# mega_shield2.net
KiCad netlist of a schematic drawn in EAGLE
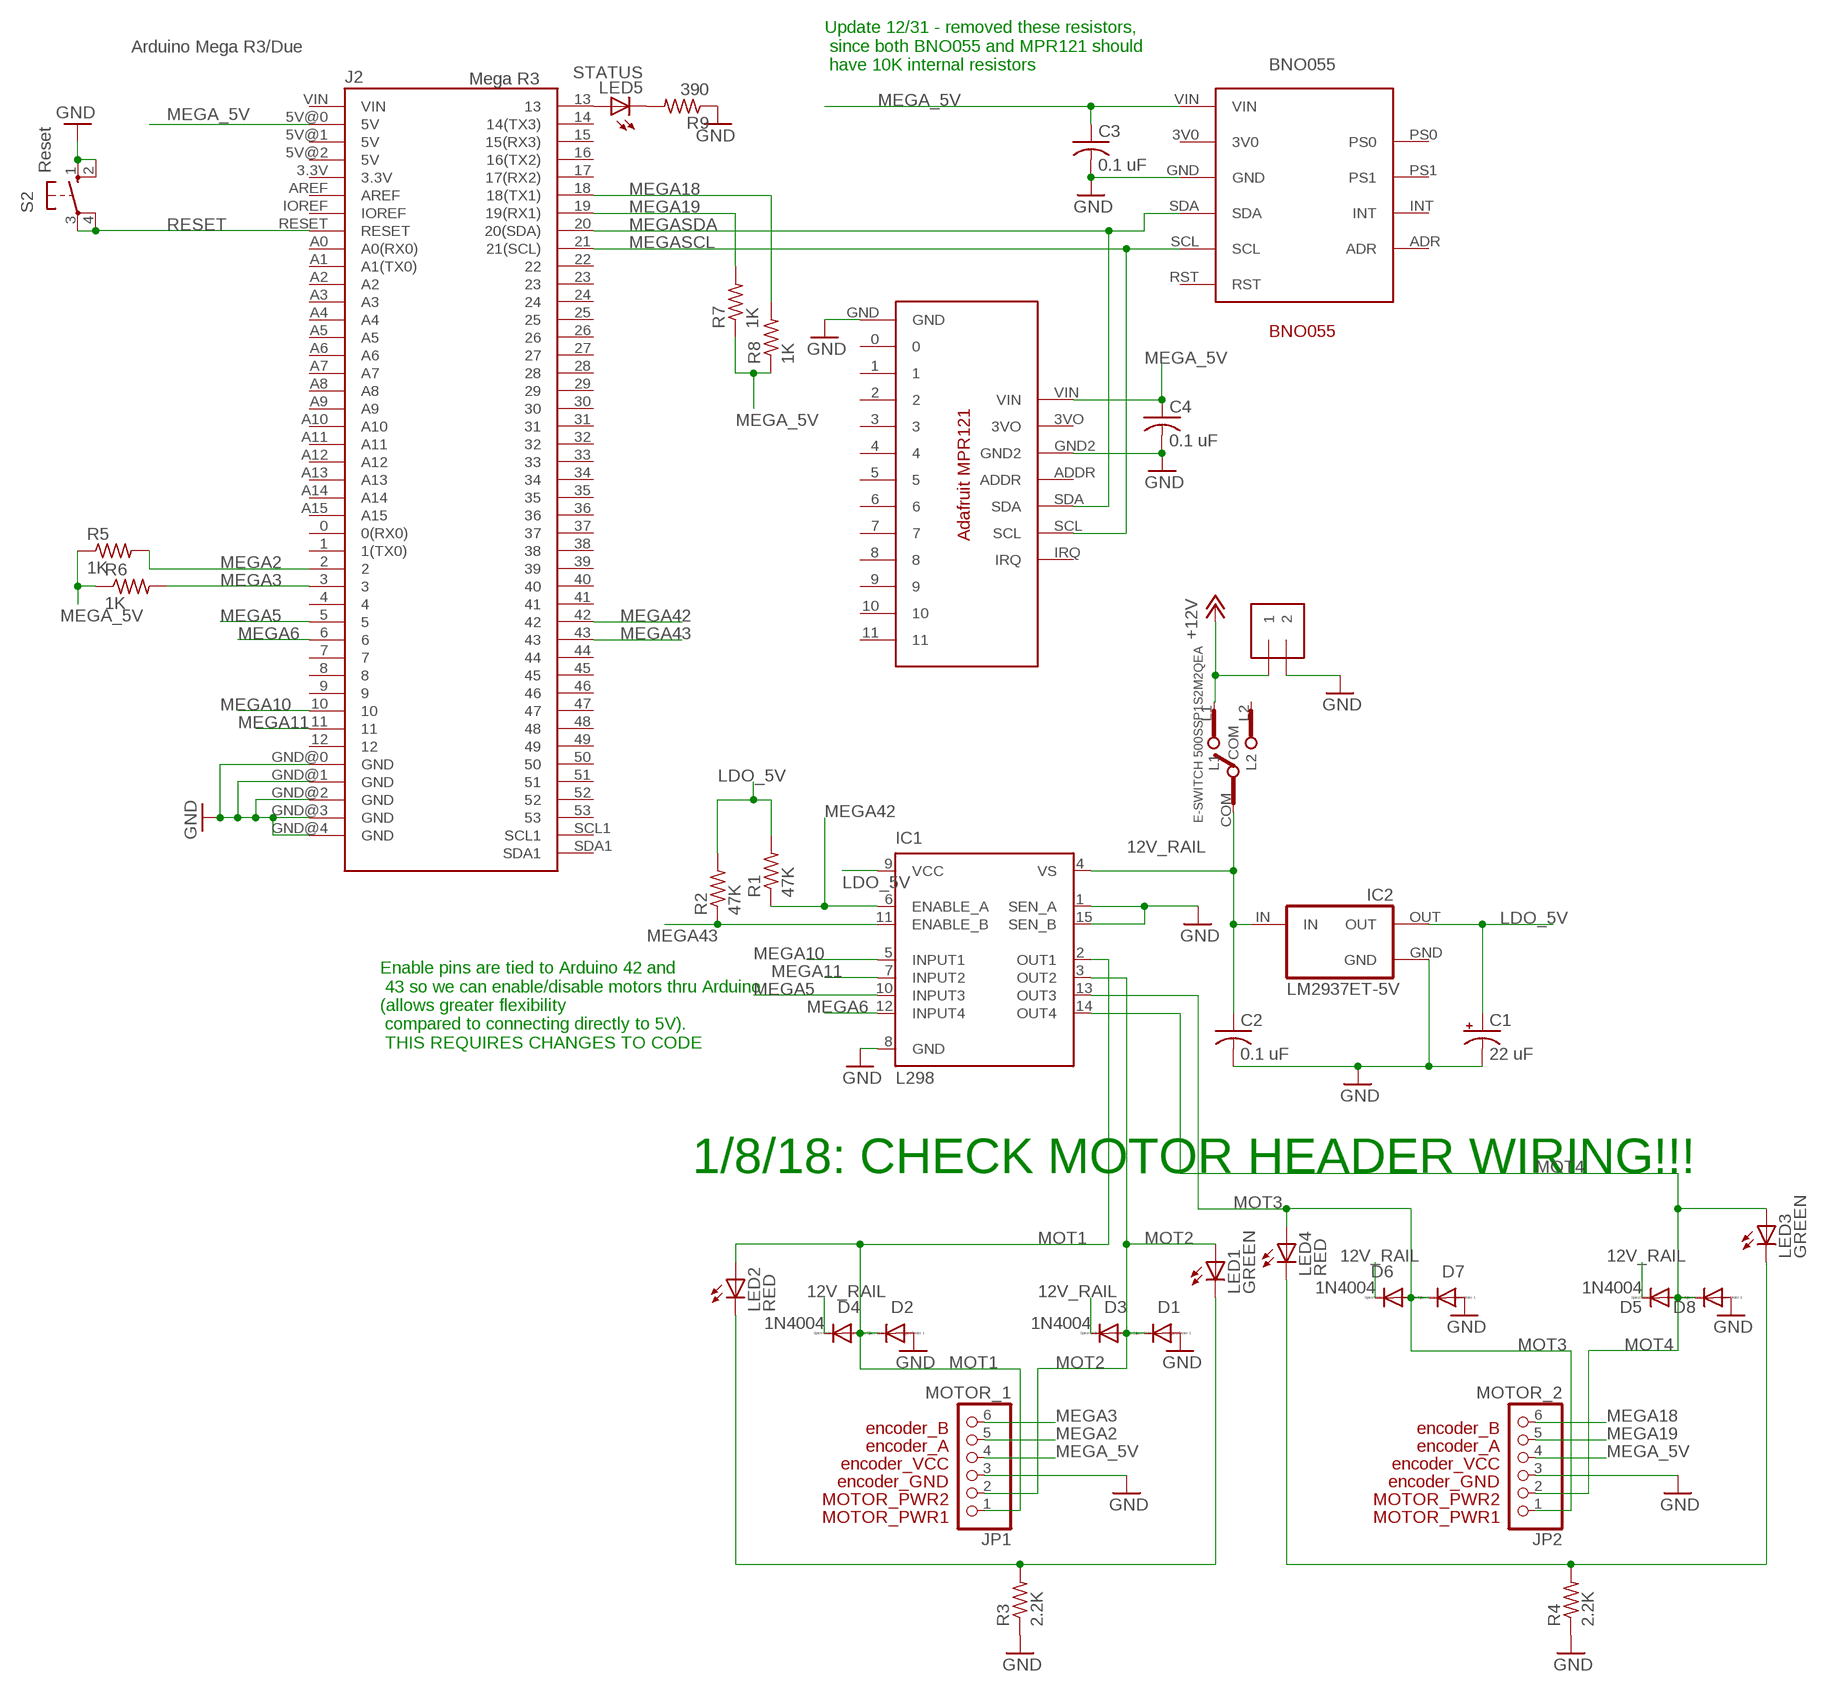
[diagram p0: schematic, sheet 1]

(export (version "E")
  (design (tool "Eeschema 10.0.6"))
  (components
    (comp (ref "12V_IN")
      (value "1X2-3.5MM")
      (footprint "eagle-import:1X2-3.5MM")
      (libsource (lib "eagle-import") (part "1X2-3.5MM"))
    )
    (comp (ref "BNO055")
      (value "BNO055")
      (footprint "eagle-import:BNO055")
      (libsource (lib "eagle-import") (part "BNO055"))
    )
    (comp (ref "C1")
      (value "22 uF")
      (footprint "eagle-import:B45181A")
      (libsource (lib "eagle-import") (part "CPOL-USB45181A"))
    )
    (comp (ref "C2")
      (value "0.1 uF")
      (footprint "eagle-import:C025-050X050")
      (libsource (lib "eagle-import") (part "C-US025-050X050"))
    )
    (comp (ref "C3")
      (value "0.1 uF")
      (footprint "eagle-import:C025-050X050")
      (libsource (lib "eagle-import") (part "C-US025-050X050"))
    )
    (comp (ref "C4")
      (value "0.1 uF")
      (footprint "eagle-import:C025-050X050")
      (libsource (lib "eagle-import") (part "C-US025-050X050"))
    )
    (comp (ref "D1")
      (value "1N4004")
      (footprint "eagle-import:DO41-10")
      (libsource (lib "eagle-import") (part "1N4004"))
    )
    (comp (ref "D2")
      (value "1N4004")
      (footprint "eagle-import:DO41-10")
      (libsource (lib "eagle-import") (part "1N4004"))
    )
    (comp (ref "D3")
      (value "1N4004")
      (footprint "eagle-import:DO41-10")
      (libsource (lib "eagle-import") (part "1N4004"))
    )
    (comp (ref "D4")
      (value "1N4004")
      (footprint "eagle-import:DO41-10")
      (libsource (lib "eagle-import") (part "1N4004"))
    )
    (comp (ref "D5")
      (value "1N4004")
      (footprint "eagle-import:DO41-10")
      (libsource (lib "eagle-import") (part "1N4004"))
    )
    (comp (ref "D6")
      (value "1N4004")
      (footprint "eagle-import:DO41-10")
      (libsource (lib "eagle-import") (part "1N4004"))
    )
    (comp (ref "D7")
      (value "1N4004")
      (footprint "eagle-import:DO41-10")
      (libsource (lib "eagle-import") (part "1N4004"))
    )
    (comp (ref "D8")
      (value "1N4004")
      (footprint "eagle-import:DO41-10")
      (libsource (lib "eagle-import") (part "1N4004"))
    )
    (comp (ref "IC1")
      (value "L298")
      (footprint "eagle-import:MULTIWATT-15")
      (fields (field (name "MPN") "L298N"))
      (libsource (lib "eagle-import") (part "L298"))
    )
    (comp (ref "IC2")
      (value "LM2937ET-5V")
      (footprint "eagle-import:TO220(V)")
      (libsource (lib "eagle-import") (part "LM2937ET-5,0"))
    )
    (comp (ref "J2")
      (value "Mega R3")
      (footprint "eagle-import:ARDUINO_MEGA")
      (libsource (lib "eagle-import") (part "ARDUINO-MEGAFULL"))
    )
    (comp (ref "JP1")
      (value "MOTOR_1")
      (footprint "eagle-import:1X06")
      (libsource (lib "eagle-import") (part "PINHD-1X6"))
    )
    (comp (ref "JP2")
      (value "MOTOR_2")
      (footprint "eagle-import:1X06")
      (libsource (lib "eagle-import") (part "PINHD-1X6"))
    )
    (comp (ref "LED1")
      (value "GREEN")
      (footprint "eagle-import:LED3MM")
      (libsource (lib "eagle-import") (part "LED3MM"))
    )
    (comp (ref "LED2")
      (value "RED")
      (footprint "eagle-import:LED3MM")
      (libsource (lib "eagle-import") (part "LED3MM"))
    )
    (comp (ref "LED3")
      (value "GREEN")
      (footprint "eagle-import:LED3MM")
      (libsource (lib "eagle-import") (part "LED3MM"))
    )
    (comp (ref "LED4")
      (value "RED")
      (footprint "eagle-import:LED3MM")
      (libsource (lib "eagle-import") (part "LED3MM"))
    )
    (comp (ref "LED5")
      (value "STATUS")
      (footprint "eagle-import:LED3MM")
      (libsource (lib "eagle-import") (part "LED3MM"))
    )
    (comp (ref "MPR121")
      (value "ADA_MPR121")
      (footprint "eagle-import:ADA_MPR121")
      (libsource (lib "eagle-import") (part "ADA_MPR121"))
    )
    (comp (ref "R1")
      (value "47K")
      (footprint "eagle-import:0207_10")
      (libsource (lib "eagle-import") (part "R-US_0207/10"))
    )
    (comp (ref "R2")
      (value "47K")
      (footprint "eagle-import:0207_10")
      (libsource (lib "eagle-import") (part "R-US_0207/10"))
    )
    (comp (ref "R3")
      (value "2.2K")
      (footprint "eagle-import:0207_10")
      (libsource (lib "eagle-import") (part "R-US_0207/10"))
    )
    (comp (ref "R4")
      (value "2.2K")
      (footprint "eagle-import:0207_10")
      (libsource (lib "eagle-import") (part "R-US_0207/10"))
    )
    (comp (ref "R5")
      (value "1K")
      (footprint "eagle-import:0207_10")
      (libsource (lib "eagle-import") (part "R-US_0207/10"))
    )
    (comp (ref "R6")
      (value "1K")
      (footprint "eagle-import:0207_10")
      (libsource (lib "eagle-import") (part "R-US_0207/10"))
    )
    (comp (ref "R7")
      (value "1K")
      (footprint "eagle-import:0207_10")
      (libsource (lib "eagle-import") (part "R-US_0207/10"))
    )
    (comp (ref "R8")
      (value "1K")
      (footprint "eagle-import:0207_10")
      (libsource (lib "eagle-import") (part "R-US_0207/10"))
    )
    (comp (ref "R9")
      (value "390")
      (footprint "eagle-import:0207_10")
      (libsource (lib "eagle-import") (part "R-US_0207/10"))
    )
    (comp (ref "S2")
      (value "Reset")
      (footprint "eagle-import:B3F-10XX")
      (fields (field (name "MPN") "B3F-1000"))
      (libsource (lib "eagle-import") (part "10-XX"))
    )
    (comp (ref "SLIDE_SW")
      (value "E-SWITCH_500SSP1S2M2QEA")
      (footprint "eagle-import:E-SWITCH_500SSP1S2M2QEA")
      (libsource (lib "eagle-import") (part "E-SWITCH_500SSP1S2M2QEA"))
    )
  )
  (nets
    (net (code "1") (name "+12V") (class "Default")
      (node (ref "12V_IN") (pin "1") (pinfunction "1_1") (pintype "passive"))
      (node (ref "SLIDE_SW") (pin "L1") (pinfunction "L1_L1") (pintype "bidirectional"))
    )
    (net (code "2") (name "/12V_RAIL") (class "Default")
      (node (ref "C2") (pin "1") (pinfunction "1_1") (pintype "passive"))
      (node (ref "D3") (pin "C") (pinfunction "C_C") (pintype "passive"))
      (node (ref "D4") (pin "C") (pinfunction "C_C") (pintype "passive"))
      (node (ref "D5") (pin "C") (pinfunction "C_C") (pintype "passive"))
      (node (ref "D6") (pin "C") (pinfunction "C_C") (pintype "passive"))
      (node (ref "IC1") (pin "4") (pinfunction "VS_4") (pintype "power_in"))
      (node (ref "IC2") (pin "IN") (pinfunction "IN_IN") (pintype "input"))
      (node (ref "SLIDE_SW") (pin "COM") (pinfunction "COM_COM") (pintype "bidirectional"))
    )
    (net (code "3") (name "/LDO_5V") (class "Default")
      (node (ref "C1") (pin "+") (pinfunction "+_+") (pintype "passive"))
      (node (ref "IC1") (pin "9") (pinfunction "VCC_9") (pintype "power_in"))
      (node (ref "IC2") (pin "OUT") (pinfunction "OUT_OUT") (pintype "output"))
      (node (ref "R1") (pin "2") (pinfunction "2_2") (pintype "passive"))
      (node (ref "R2") (pin "2") (pinfunction "2_2") (pintype "passive"))
    )
    (net (code "4") (name "/MEGA2") (class "Default")
      (node (ref "J2") (pin "2") (pinfunction "2_2") (pintype "bidirectional"))
      (node (ref "JP1") (pin "5") (pinfunction "5_5") (pintype "passive"))
      (node (ref "R5") (pin "2") (pinfunction "2_2") (pintype "passive"))
    )
    (net (code "5") (name "/MEGA3") (class "Default")
      (node (ref "J2") (pin "3") (pinfunction "3_3") (pintype "bidirectional"))
      (node (ref "JP1") (pin "6") (pinfunction "6_6") (pintype "passive"))
      (node (ref "R6") (pin "2") (pinfunction "2_2") (pintype "passive"))
    )
    (net (code "6") (name "/MEGA5") (class "Default")
      (node (ref "IC1") (pin "10") (pinfunction "INPUT3_10") (pintype "input"))
      (node (ref "J2") (pin "5") (pinfunction "5_5") (pintype "bidirectional"))
    )
    (net (code "7") (name "/MEGA6") (class "Default")
      (node (ref "IC1") (pin "12") (pinfunction "INPUT4_12") (pintype "input"))
      (node (ref "J2") (pin "6") (pinfunction "6_6") (pintype "bidirectional"))
    )
    (net (code "8") (name "/MEGA10") (class "Default")
      (node (ref "IC1") (pin "5") (pinfunction "INPUT1_5") (pintype "input"))
      (node (ref "J2") (pin "10") (pinfunction "10_10") (pintype "bidirectional"))
    )
    (net (code "9") (name "/MEGA11") (class "Default")
      (node (ref "IC1") (pin "7") (pinfunction "INPUT2_7") (pintype "input"))
      (node (ref "J2") (pin "11") (pinfunction "11_11") (pintype "bidirectional"))
    )
    (net (code "10") (name "/MEGA18") (class "Default")
      (node (ref "J2") (pin "18") (pinfunction "18(TX1)_18") (pintype "bidirectional"))
      (node (ref "JP2") (pin "6") (pinfunction "6_6") (pintype "passive"))
      (node (ref "R8") (pin "2") (pinfunction "2_2") (pintype "passive"))
    )
    (net (code "11") (name "/MEGA19") (class "Default")
      (node (ref "J2") (pin "19") (pinfunction "19(RX1)_19") (pintype "bidirectional"))
      (node (ref "JP2") (pin "5") (pinfunction "5_5") (pintype "passive"))
      (node (ref "R7") (pin "2") (pinfunction "2_2") (pintype "passive"))
    )
    (net (code "12") (name "/MEGA42") (class "Default")
      (node (ref "IC1") (pin "6") (pinfunction "ENABLE_A_6") (pintype "input"))
      (node (ref "J2") (pin "42") (pinfunction "42_42") (pintype "bidirectional"))
      (node (ref "R1") (pin "1") (pinfunction "1_1") (pintype "passive"))
    )
    (net (code "13") (name "/MEGA43") (class "Default")
      (node (ref "IC1") (pin "11") (pinfunction "ENABLE_B_11") (pintype "input"))
      (node (ref "J2") (pin "43") (pinfunction "43_43") (pintype "bidirectional"))
      (node (ref "R2") (pin "1") (pinfunction "1_1") (pintype "passive"))
    )
    (net (code "14") (name "/MEGASCL") (class "Default")
      (node (ref "BNO055") (pin "SCL") (pinfunction "SCL_SCL") (pintype "bidirectional"))
      (node (ref "J2") (pin "21") (pinfunction "21(SCL)_21") (pintype "bidirectional"))
      (node (ref "MPR121") (pin "SCL") (pinfunction "SCL_SCL") (pintype "bidirectional"))
    )
    (net (code "15") (name "/MEGASDA") (class "Default")
      (node (ref "BNO055") (pin "SDA") (pinfunction "SDA_SDA") (pintype "bidirectional"))
      (node (ref "J2") (pin "20") (pinfunction "20(SDA)_20") (pintype "bidirectional"))
      (node (ref "MPR121") (pin "SDA") (pinfunction "SDA_SDA") (pintype "bidirectional"))
    )
    (net (code "16") (name "/MEGA_5V") (class "Default")
      (node (ref "BNO055") (pin "VIN") (pinfunction "VIN_VIN") (pintype "bidirectional"))
      (node (ref "C3") (pin "1") (pinfunction "1_1") (pintype "passive"))
      (node (ref "C4") (pin "1") (pinfunction "1_1") (pintype "passive"))
      (node (ref "J2") (pin "5V@0") (pinfunction "5V_5V@0") (pintype "bidirectional"))
      (node (ref "JP1") (pin "4") (pinfunction "4_4") (pintype "passive"))
      (node (ref "JP2") (pin "4") (pinfunction "4_4") (pintype "passive"))
      (node (ref "MPR121") (pin "VIN") (pinfunction "VIN_VIN") (pintype "bidirectional"))
      (node (ref "R5") (pin "1") (pinfunction "1_1") (pintype "passive"))
      (node (ref "R6") (pin "1") (pinfunction "1_1") (pintype "passive"))
      (node (ref "R7") (pin "1") (pinfunction "1_1") (pintype "passive"))
      (node (ref "R8") (pin "1") (pinfunction "1_1") (pintype "passive"))
    )
    (net (code "17") (name "/MOT1") (class "Default")
      (node (ref "D2") (pin "C") (pinfunction "C_C") (pintype "passive"))
      (node (ref "D4") (pin "A") (pinfunction "A_A") (pintype "passive"))
      (node (ref "IC1") (pin "2") (pinfunction "OUT1_2") (pintype "output"))
      (node (ref "JP1") (pin "1") (pinfunction "1_1") (pintype "passive"))
      (node (ref "LED2") (pin "A") (pinfunction "A_A") (pintype "passive"))
    )
    (net (code "18") (name "/MOT2") (class "Default")
      (node (ref "D1") (pin "C") (pinfunction "C_C") (pintype "passive"))
      (node (ref "D3") (pin "A") (pinfunction "A_A") (pintype "passive"))
      (node (ref "IC1") (pin "3") (pinfunction "OUT2_3") (pintype "output"))
      (node (ref "JP1") (pin "2") (pinfunction "2_2") (pintype "passive"))
      (node (ref "LED1") (pin "A") (pinfunction "A_A") (pintype "passive"))
    )
    (net (code "19") (name "/MOT3") (class "Default")
      (node (ref "D6") (pin "A") (pinfunction "A_A") (pintype "passive"))
      (node (ref "D7") (pin "C") (pinfunction "C_C") (pintype "passive"))
      (node (ref "IC1") (pin "13") (pinfunction "OUT3_13") (pintype "output"))
      (node (ref "JP2") (pin "1") (pinfunction "1_1") (pintype "passive"))
      (node (ref "LED4") (pin "A") (pinfunction "A_A") (pintype "passive"))
    )
    (net (code "20") (name "/MOT4") (class "Default")
      (node (ref "D5") (pin "A") (pinfunction "A_A") (pintype "passive"))
      (node (ref "D8") (pin "C") (pinfunction "C_C") (pintype "passive"))
      (node (ref "IC1") (pin "14") (pinfunction "OUT4_14") (pintype "output"))
      (node (ref "JP2") (pin "2") (pinfunction "2_2") (pintype "passive"))
      (node (ref "LED3") (pin "A") (pinfunction "A_A") (pintype "passive"))
    )
    (net (code "21") (name "/RESET") (class "Default")
      (node (ref "J2") (pin "RESET") (pinfunction "RESET_RESET") (pintype "bidirectional"))
      (node (ref "S2") (pin "3") (pinfunction "P_3") (pintype "passive"))
      (node (ref "S2") (pin "4") (pinfunction "P1_4") (pintype "passive"))
    )
    (net (code "22") (name "GND") (class "Default")
      (node (ref "12V_IN") (pin "2") (pinfunction "2_2") (pintype "passive"))
      (node (ref "BNO055") (pin "GND") (pinfunction "GND_GND") (pintype "bidirectional"))
      (node (ref "C1") (pin "-") (pinfunction "-_-") (pintype "passive"))
      (node (ref "C2") (pin "2") (pinfunction "2_2") (pintype "passive"))
      (node (ref "C3") (pin "2") (pinfunction "2_2") (pintype "passive"))
      (node (ref "C4") (pin "2") (pinfunction "2_2") (pintype "passive"))
      (node (ref "D1") (pin "A") (pinfunction "A_A") (pintype "passive"))
      (node (ref "D2") (pin "A") (pinfunction "A_A") (pintype "passive"))
      (node (ref "D7") (pin "A") (pinfunction "A_A") (pintype "passive"))
      (node (ref "D8") (pin "A") (pinfunction "A_A") (pintype "passive"))
      (node (ref "IC1") (pin "1") (pinfunction "SEN_A_1") (pintype "input"))
      (node (ref "IC1") (pin "15") (pinfunction "SEN_B_15") (pintype "input"))
      (node (ref "IC1") (pin "8") (pinfunction "GND_8") (pintype "power_in"))
      (node (ref "IC2") (pin "GND") (pinfunction "GND_GND") (pintype "power_in"))
      (node (ref "J2") (pin "GND@0") (pinfunction "GND_GND@0") (pintype "bidirectional"))
      (node (ref "J2") (pin "GND@1") (pinfunction "GND_GND@1") (pintype "bidirectional"))
      (node (ref "J2") (pin "GND@2") (pinfunction "GND_GND@2") (pintype "bidirectional"))
      (node (ref "J2") (pin "GND@3") (pinfunction "GND_GND@3") (pintype "bidirectional"))
      (node (ref "J2") (pin "GND@4") (pinfunction "GND_GND@4") (pintype "bidirectional"))
      (node (ref "JP1") (pin "3") (pinfunction "3_3") (pintype "passive"))
      (node (ref "JP2") (pin "3") (pinfunction "3_3") (pintype "passive"))
      (node (ref "MPR121") (pin "GND") (pinfunction "GND_GND") (pintype "bidirectional"))
      (node (ref "MPR121") (pin "GND2") (pinfunction "GND2_GND2") (pintype "bidirectional"))
      (node (ref "R3") (pin "1") (pinfunction "1_1") (pintype "passive"))
      (node (ref "R4") (pin "1") (pinfunction "1_1") (pintype "passive"))
      (node (ref "R9") (pin "1") (pinfunction "1_1") (pintype "passive"))
      (node (ref "S2") (pin "1") (pinfunction "S_1") (pintype "passive"))
      (node (ref "S2") (pin "2") (pinfunction "S1_2") (pintype "passive"))
    )
    (net (code "23") (name "Net-(J2-Pad13)") (class "Default")
      (node (ref "J2") (pin "13") (pinfunction "13_13") (pintype "bidirectional"))
      (node (ref "LED5") (pin "A") (pinfunction "A_A") (pintype "passive"))
    )
    (net (code "24") (name "Net-(LED1-C)") (class "Default")
      (node (ref "LED1") (pin "K") (pinfunction "C_K") (pintype "passive"))
      (node (ref "LED2") (pin "K") (pinfunction "C_K") (pintype "passive"))
      (node (ref "R3") (pin "2") (pinfunction "2_2") (pintype "passive"))
    )
    (net (code "25") (name "Net-(LED3-C)") (class "Default")
      (node (ref "LED3") (pin "K") (pinfunction "C_K") (pintype "passive"))
      (node (ref "LED4") (pin "K") (pinfunction "C_K") (pintype "passive"))
      (node (ref "R4") (pin "2") (pinfunction "2_2") (pintype "passive"))
    )
    (net (code "26") (name "Net-(LED5-C)") (class "Default")
      (node (ref "LED5") (pin "K") (pinfunction "C_K") (pintype "passive"))
      (node (ref "R9") (pin "2") (pinfunction "2_2") (pintype "passive"))
    )
    (net (code "27") (name "unconnected-(BNO055-Pad3V0)") (class "Default")
      (node (ref "BNO055") (pin "3V0") (pinfunction "3V0_3V0") (pintype "bidirectional"))
    )
    (net (code "28") (name "unconnected-(BNO055-PadADR)") (class "Default")
      (node (ref "BNO055") (pin "ADR") (pinfunction "ADR_ADR") (pintype "bidirectional"))
    )
    (net (code "29") (name "unconnected-(BNO055-PadINT)") (class "Default")
      (node (ref "BNO055") (pin "INT") (pinfunction "INT_INT") (pintype "bidirectional"))
    )
    (net (code "30") (name "unconnected-(BNO055-PadPS0)") (class "Default")
      (node (ref "BNO055") (pin "PS0") (pinfunction "PS0_PS0") (pintype "bidirectional"))
    )
    (net (code "31") (name "unconnected-(BNO055-PadPS1)") (class "Default")
      (node (ref "BNO055") (pin "PS1") (pinfunction "PS1_PS1") (pintype "bidirectional"))
    )
    (net (code "32") (name "unconnected-(BNO055-PadRST)") (class "Default")
      (node (ref "BNO055") (pin "RST") (pinfunction "RST_RST") (pintype "bidirectional"))
    )
    (net (code "33") (name "unconnected-(J2-0(RX0)-Pad0)") (class "Default")
      (node (ref "J2") (pin "0") (pinfunction "0(RX0)_0") (pintype "bidirectional"))
    )
    (net (code "34") (name "unconnected-(J2-1(TX0)-Pad1)") (class "Default")
      (node (ref "J2") (pin "1") (pinfunction "1(TX0)_1") (pintype "bidirectional"))
    )
    (net (code "35") (name "unconnected-(J2-5V-Pad5V@1)") (class "Default")
      (node (ref "J2") (pin "5V@1") (pinfunction "5V_5V@1") (pintype "bidirectional"))
    )
    (net (code "36") (name "unconnected-(J2-5V-Pad5V@2)") (class "Default")
      (node (ref "J2") (pin "5V@2") (pinfunction "5V_5V@2") (pintype "bidirectional"))
    )
    (net (code "37") (name "unconnected-(J2-14(TX3)-Pad14)") (class "Default")
      (node (ref "J2") (pin "14") (pinfunction "14(TX3)_14") (pintype "bidirectional"))
    )
    (net (code "38") (name "unconnected-(J2-15(RX3)-Pad15)") (class "Default")
      (node (ref "J2") (pin "15") (pinfunction "15(RX3)_15") (pintype "bidirectional"))
    )
    (net (code "39") (name "unconnected-(J2-16(TX2)-Pad16)") (class "Default")
      (node (ref "J2") (pin "16") (pinfunction "16(TX2)_16") (pintype "bidirectional"))
    )
    (net (code "40") (name "unconnected-(J2-17(RX2)-Pad17)") (class "Default")
      (node (ref "J2") (pin "17") (pinfunction "17(RX2)_17") (pintype "bidirectional"))
    )
    (net (code "41") (name "unconnected-(J2-A0(RX0)-PadA0)") (class "Default")
      (node (ref "J2") (pin "A0") (pinfunction "A0(RX0)_A0") (pintype "bidirectional"))
    )
    (net (code "42") (name "unconnected-(J2-A1(TX0)-PadA1)") (class "Default")
      (node (ref "J2") (pin "A1") (pinfunction "A1(TX0)_A1") (pintype "bidirectional"))
    )
    (net (code "43") (name "unconnected-(J2-Pad3.3V)") (class "Default")
      (node (ref "J2") (pin "3.3V") (pinfunction "3.3V_3.3V") (pintype "bidirectional"))
    )
    (net (code "44") (name "unconnected-(J2-Pad4)") (class "Default")
      (node (ref "J2") (pin "4") (pinfunction "4_4") (pintype "bidirectional"))
    )
    (net (code "45") (name "unconnected-(J2-Pad7)") (class "Default")
      (node (ref "J2") (pin "7") (pinfunction "7_7") (pintype "bidirectional"))
    )
    (net (code "46") (name "unconnected-(J2-Pad8)") (class "Default")
      (node (ref "J2") (pin "8") (pinfunction "8_8") (pintype "bidirectional"))
    )
    (net (code "47") (name "unconnected-(J2-Pad9)") (class "Default")
      (node (ref "J2") (pin "9") (pinfunction "9_9") (pintype "bidirectional"))
    )
    (net (code "48") (name "unconnected-(J2-Pad12)") (class "Default")
      (node (ref "J2") (pin "12") (pinfunction "12_12") (pintype "bidirectional"))
    )
    (net (code "49") (name "unconnected-(J2-Pad22)") (class "Default")
      (node (ref "J2") (pin "22") (pinfunction "22_22") (pintype "bidirectional"))
    )
    (net (code "50") (name "unconnected-(J2-Pad23)") (class "Default")
      (node (ref "J2") (pin "23") (pinfunction "23_23") (pintype "bidirectional"))
    )
    (net (code "51") (name "unconnected-(J2-Pad24)") (class "Default")
      (node (ref "J2") (pin "24") (pinfunction "24_24") (pintype "bidirectional"))
    )
    (net (code "52") (name "unconnected-(J2-Pad25)") (class "Default")
      (node (ref "J2") (pin "25") (pinfunction "25_25") (pintype "bidirectional"))
    )
    (net (code "53") (name "unconnected-(J2-Pad26)") (class "Default")
      (node (ref "J2") (pin "26") (pinfunction "26_26") (pintype "bidirectional"))
    )
    (net (code "54") (name "unconnected-(J2-Pad27)") (class "Default")
      (node (ref "J2") (pin "27") (pinfunction "27_27") (pintype "bidirectional"))
    )
    (net (code "55") (name "unconnected-(J2-Pad28)") (class "Default")
      (node (ref "J2") (pin "28") (pinfunction "28_28") (pintype "bidirectional"))
    )
    (net (code "56") (name "unconnected-(J2-Pad29)") (class "Default")
      (node (ref "J2") (pin "29") (pinfunction "29_29") (pintype "bidirectional"))
    )
    (net (code "57") (name "unconnected-(J2-Pad30)") (class "Default")
      (node (ref "J2") (pin "30") (pinfunction "30_30") (pintype "bidirectional"))
    )
    (net (code "58") (name "unconnected-(J2-Pad31)") (class "Default")
      (node (ref "J2") (pin "31") (pinfunction "31_31") (pintype "bidirectional"))
    )
    (net (code "59") (name "unconnected-(J2-Pad32)") (class "Default")
      (node (ref "J2") (pin "32") (pinfunction "32_32") (pintype "bidirectional"))
    )
    (net (code "60") (name "unconnected-(J2-Pad33)") (class "Default")
      (node (ref "J2") (pin "33") (pinfunction "33_33") (pintype "bidirectional"))
    )
    (net (code "61") (name "unconnected-(J2-Pad34)") (class "Default")
      (node (ref "J2") (pin "34") (pinfunction "34_34") (pintype "bidirectional"))
    )
    (net (code "62") (name "unconnected-(J2-Pad35)") (class "Default")
      (node (ref "J2") (pin "35") (pinfunction "35_35") (pintype "bidirectional"))
    )
    (net (code "63") (name "unconnected-(J2-Pad36)") (class "Default")
      (node (ref "J2") (pin "36") (pinfunction "36_36") (pintype "bidirectional"))
    )
    (net (code "64") (name "unconnected-(J2-Pad37)") (class "Default")
      (node (ref "J2") (pin "37") (pinfunction "37_37") (pintype "bidirectional"))
    )
    (net (code "65") (name "unconnected-(J2-Pad38)") (class "Default")
      (node (ref "J2") (pin "38") (pinfunction "38_38") (pintype "bidirectional"))
    )
    (net (code "66") (name "unconnected-(J2-Pad39)") (class "Default")
      (node (ref "J2") (pin "39") (pinfunction "39_39") (pintype "bidirectional"))
    )
    (net (code "67") (name "unconnected-(J2-Pad40)") (class "Default")
      (node (ref "J2") (pin "40") (pinfunction "40_40") (pintype "bidirectional"))
    )
    (net (code "68") (name "unconnected-(J2-Pad41)") (class "Default")
      (node (ref "J2") (pin "41") (pinfunction "41_41") (pintype "bidirectional"))
    )
    (net (code "69") (name "unconnected-(J2-Pad44)") (class "Default")
      (node (ref "J2") (pin "44") (pinfunction "44_44") (pintype "bidirectional"))
    )
    (net (code "70") (name "unconnected-(J2-Pad45)") (class "Default")
      (node (ref "J2") (pin "45") (pinfunction "45_45") (pintype "bidirectional"))
    )
    (net (code "71") (name "unconnected-(J2-Pad46)") (class "Default")
      (node (ref "J2") (pin "46") (pinfunction "46_46") (pintype "bidirectional"))
    )
    (net (code "72") (name "unconnected-(J2-Pad47)") (class "Default")
      (node (ref "J2") (pin "47") (pinfunction "47_47") (pintype "bidirectional"))
    )
    (net (code "73") (name "unconnected-(J2-Pad48)") (class "Default")
      (node (ref "J2") (pin "48") (pinfunction "48_48") (pintype "bidirectional"))
    )
    (net (code "74") (name "unconnected-(J2-Pad49)") (class "Default")
      (node (ref "J2") (pin "49") (pinfunction "49_49") (pintype "bidirectional"))
    )
    (net (code "75") (name "unconnected-(J2-Pad50)") (class "Default")
      (node (ref "J2") (pin "50") (pinfunction "50_50") (pintype "bidirectional"))
    )
    (net (code "76") (name "unconnected-(J2-Pad51)") (class "Default")
      (node (ref "J2") (pin "51") (pinfunction "51_51") (pintype "bidirectional"))
    )
    (net (code "77") (name "unconnected-(J2-Pad52)") (class "Default")
      (node (ref "J2") (pin "52") (pinfunction "52_52") (pintype "bidirectional"))
    )
    (net (code "78") (name "unconnected-(J2-Pad53)") (class "Default")
      (node (ref "J2") (pin "53") (pinfunction "53_53") (pintype "bidirectional"))
    )
    (net (code "79") (name "unconnected-(J2-PadA2)") (class "Default")
      (node (ref "J2") (pin "A2") (pinfunction "A2_A2") (pintype "bidirectional"))
    )
    (net (code "80") (name "unconnected-(J2-PadA3)") (class "Default")
      (node (ref "J2") (pin "A3") (pinfunction "A3_A3") (pintype "bidirectional"))
    )
    (net (code "81") (name "unconnected-(J2-PadA4)") (class "Default")
      (node (ref "J2") (pin "A4") (pinfunction "A4_A4") (pintype "bidirectional"))
    )
    (net (code "82") (name "unconnected-(J2-PadA5)") (class "Default")
      (node (ref "J2") (pin "A5") (pinfunction "A5_A5") (pintype "bidirectional"))
    )
    (net (code "83") (name "unconnected-(J2-PadA6)") (class "Default")
      (node (ref "J2") (pin "A6") (pinfunction "A6_A6") (pintype "bidirectional"))
    )
    (net (code "84") (name "unconnected-(J2-PadA7)") (class "Default")
      (node (ref "J2") (pin "A7") (pinfunction "A7_A7") (pintype "bidirectional"))
    )
    (net (code "85") (name "unconnected-(J2-PadA8)") (class "Default")
      (node (ref "J2") (pin "A8") (pinfunction "A8_A8") (pintype "bidirectional"))
    )
    (net (code "86") (name "unconnected-(J2-PadA9)") (class "Default")
      (node (ref "J2") (pin "A9") (pinfunction "A9_A9") (pintype "bidirectional"))
    )
    (net (code "87") (name "unconnected-(J2-PadA10)") (class "Default")
      (node (ref "J2") (pin "A10") (pinfunction "A10_A10") (pintype "bidirectional"))
    )
    (net (code "88") (name "unconnected-(J2-PadA11)") (class "Default")
      (node (ref "J2") (pin "A11") (pinfunction "A11_A11") (pintype "bidirectional"))
    )
    (net (code "89") (name "unconnected-(J2-PadA12)") (class "Default")
      (node (ref "J2") (pin "A12") (pinfunction "A12_A12") (pintype "bidirectional"))
    )
    (net (code "90") (name "unconnected-(J2-PadA13)") (class "Default")
      (node (ref "J2") (pin "A13") (pinfunction "A13_A13") (pintype "bidirectional"))
    )
    (net (code "91") (name "unconnected-(J2-PadA14)") (class "Default")
      (node (ref "J2") (pin "A14") (pinfunction "A14_A14") (pintype "bidirectional"))
    )
    (net (code "92") (name "unconnected-(J2-PadA15)") (class "Default")
      (node (ref "J2") (pin "A15") (pinfunction "A15_A15") (pintype "bidirectional"))
    )
    (net (code "93") (name "unconnected-(J2-PadAREF)") (class "Default")
      (node (ref "J2") (pin "AREF") (pinfunction "AREF_AREF") (pintype "bidirectional"))
    )
    (net (code "94") (name "unconnected-(J2-PadIOREF)") (class "Default")
      (node (ref "J2") (pin "IOREF") (pinfunction "IOREF_IOREF") (pintype "bidirectional"))
    )
    (net (code "95") (name "unconnected-(J2-PadSCL1)") (class "Default")
      (node (ref "J2") (pin "SCL1") (pinfunction "SCL1_SCL1") (pintype "bidirectional"))
    )
    (net (code "96") (name "unconnected-(J2-PadSDA1)") (class "Default")
      (node (ref "J2") (pin "SDA1") (pinfunction "SDA1_SDA1") (pintype "bidirectional"))
    )
    (net (code "97") (name "unconnected-(J2-PadVIN)") (class "Default")
      (node (ref "J2") (pin "VIN") (pinfunction "VIN_VIN") (pintype "bidirectional"))
    )
    (net (code "98") (name "unconnected-(MPR121-Pad0)") (class "Default")
      (node (ref "MPR121") (pin "0") (pinfunction "0_0") (pintype "bidirectional"))
    )
    (net (code "99") (name "unconnected-(MPR121-Pad1)") (class "Default")
      (node (ref "MPR121") (pin "1") (pinfunction "1_1") (pintype "bidirectional"))
    )
    (net (code "100") (name "unconnected-(MPR121-Pad2)") (class "Default")
      (node (ref "MPR121") (pin "2") (pinfunction "2_2") (pintype "bidirectional"))
    )
    (net (code "101") (name "unconnected-(MPR121-Pad3)") (class "Default")
      (node (ref "MPR121") (pin "3") (pinfunction "3_3") (pintype "bidirectional"))
    )
    (net (code "102") (name "unconnected-(MPR121-Pad3VO)") (class "Default")
      (node (ref "MPR121") (pin "3VO") (pinfunction "3VO_3VO") (pintype "bidirectional"))
    )
    (net (code "103") (name "unconnected-(MPR121-Pad4)") (class "Default")
      (node (ref "MPR121") (pin "4") (pinfunction "4_4") (pintype "bidirectional"))
    )
    (net (code "104") (name "unconnected-(MPR121-Pad5)") (class "Default")
      (node (ref "MPR121") (pin "5") (pinfunction "5_5") (pintype "bidirectional"))
    )
    (net (code "105") (name "unconnected-(MPR121-Pad6)") (class "Default")
      (node (ref "MPR121") (pin "6") (pinfunction "6_6") (pintype "bidirectional"))
    )
    (net (code "106") (name "unconnected-(MPR121-Pad7)") (class "Default")
      (node (ref "MPR121") (pin "7") (pinfunction "7_7") (pintype "bidirectional"))
    )
    (net (code "107") (name "unconnected-(MPR121-Pad8)") (class "Default")
      (node (ref "MPR121") (pin "8") (pinfunction "8_8") (pintype "bidirectional"))
    )
    (net (code "108") (name "unconnected-(MPR121-Pad9)") (class "Default")
      (node (ref "MPR121") (pin "9") (pinfunction "9_9") (pintype "bidirectional"))
    )
    (net (code "109") (name "unconnected-(MPR121-Pad10)") (class "Default")
      (node (ref "MPR121") (pin "10") (pinfunction "10_10") (pintype "bidirectional"))
    )
    (net (code "110") (name "unconnected-(MPR121-Pad11)") (class "Default")
      (node (ref "MPR121") (pin "11") (pinfunction "11_11") (pintype "bidirectional"))
    )
    (net (code "111") (name "unconnected-(MPR121-PadADDR)") (class "Default")
      (node (ref "MPR121") (pin "ADDR") (pinfunction "ADDR_ADDR") (pintype "bidirectional"))
    )
    (net (code "112") (name "unconnected-(MPR121-PadIRQ)") (class "Default")
      (node (ref "MPR121") (pin "IRQ") (pinfunction "IRQ_IRQ") (pintype "bidirectional"))
    )
    (net (code "113") (name "unconnected-(SLIDE_SW-PadL2)") (class "Default")
      (node (ref "SLIDE_SW") (pin "L2") (pinfunction "L2_L2") (pintype "bidirectional"))
    )
  )
)
